# CLK_PWR.net
KiCad netlist of a schematic drawn in Altium Designer
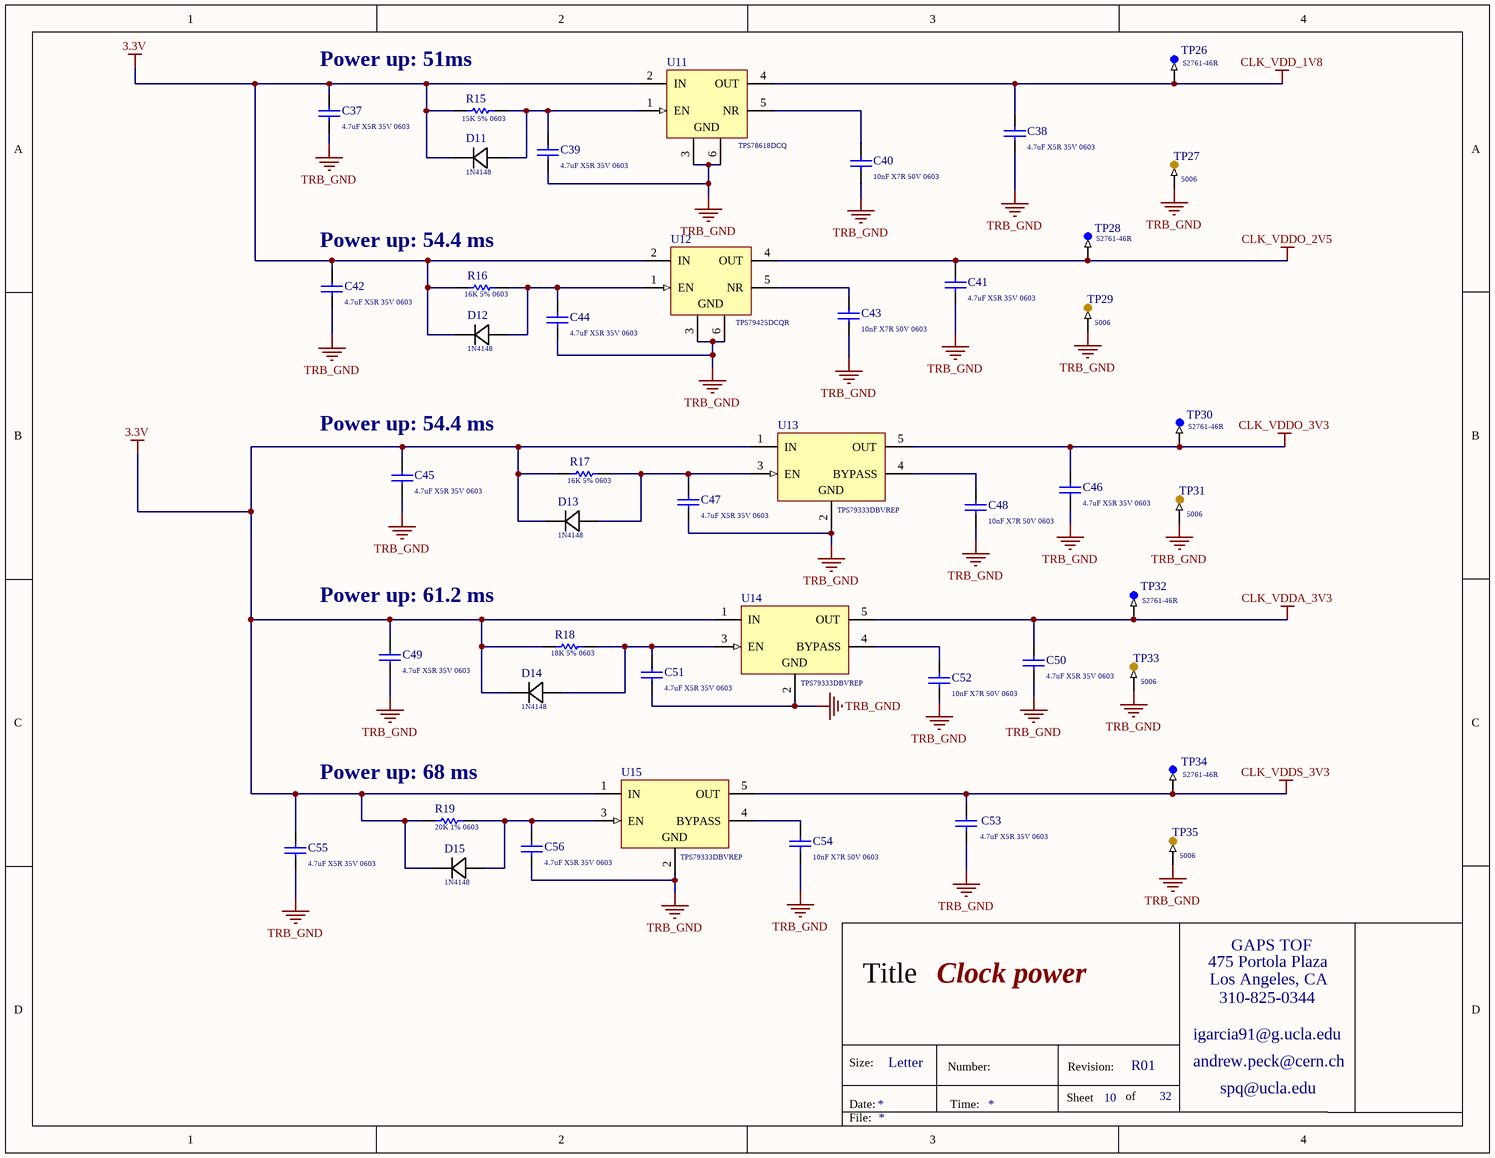
[diagram p0: CLK_PWR.SchDoc]

(export (version "E")
  (design (tool "Eeschema 10.0.6"))
  (components
    (comp (ref "C37")
      (value "Cap_Murata_ZRB18AR6YA475ME05L_4.7uF")
      (footprint "Cap_Murata_ZRB18AR6YA475ME05L_4.7uF")
      (description "CAP CER 4.7uF 35V X5R 0603")
      (fields (field (name "CAPACITANCE") "4.7uF X5R 35V 0603"))
      (libsource (lib "Cap_Murata_ZRB18AR6YA475ME05L_4.7uF") (part "Cap_Murata_ZRB18AR6YA475ME05L_4.7uF"))
    )
    (comp (ref "C38")
      (value "Cap_Murata_ZRB18AR6YA475ME05L_4.7uF")
      (footprint "Cap_Murata_ZRB18AR6YA475ME05L_4.7uF")
      (description "CAP CER 4.7uF 35V X5R 0603")
      (fields (field (name "CAPACITANCE") "4.7uF X5R 35V 0603"))
      (libsource (lib "Cap_Murata_ZRB18AR6YA475ME05L_4.7uF") (part "Cap_Murata_ZRB18AR6YA475ME05L_4.7uF"))
    )
    (comp (ref "C39")
      (value "Cap_Murata_ZRB18AR6YA475ME05L_4.7uF")
      (footprint "Cap_Murata_ZRB18AR6YA475ME05L_4.7uF")
      (description "CAP CER 4.7uF 35V X5R 0603")
      (fields (field (name "CAPACITANCE") "4.7uF X5R 35V 0603"))
      (libsource (lib "Cap_Murata_ZRB18AR6YA475ME05L_4.7uF") (part "Cap_Murata_ZRB18AR6YA475ME05L_4.7uF"))
    )
    (comp (ref "C40")
      (value "Cap_Kemet_C0603C103J5RACTU_eec")
      (footprint "Kemet_C0603_0")
      (description "CAP CER 10nF 50V X7R 0603")
      (fields
        (field (name "PART NUMBER") "C0603C103J5RACTU")
        (field (name "MANUFACTURER") "Kemet")
        (field (name "CAPACITANCE") "10nF X7R 50V 0603")
      )
      (libsource (lib "Cap_Kemet_C0603C103J5RACTU_10nF") (part "Cap_Kemet_C0603C103J5RACTU_eec"))
    )
    (comp (ref "C41")
      (value "Cap_Murata_ZRB18AR6YA475ME05L_4.7uF")
      (footprint "Cap_Murata_ZRB18AR6YA475ME05L_4.7uF")
      (description "CAP CER 4.7uF 35V X5R 0603")
      (fields (field (name "CAPACITANCE") "4.7uF X5R 35V 0603"))
      (libsource (lib "Cap_Murata_ZRB18AR6YA475ME05L_4.7uF") (part "Cap_Murata_ZRB18AR6YA475ME05L_4.7uF"))
    )
    (comp (ref "C42")
      (value "Cap_Murata_ZRB18AR6YA475ME05L_4.7uF")
      (footprint "Cap_Murata_ZRB18AR6YA475ME05L_4.7uF")
      (description "CAP CER 4.7uF 35V X5R 0603")
      (fields (field (name "CAPACITANCE") "4.7uF X5R 35V 0603"))
      (libsource (lib "Cap_Murata_ZRB18AR6YA475ME05L_4.7uF") (part "Cap_Murata_ZRB18AR6YA475ME05L_4.7uF"))
    )
    (comp (ref "C43")
      (value "Cap_Kemet_C0603C103J5RACTU_eec")
      (footprint "Kemet_C0603_0")
      (description "CAP CER 10nF 50V X7R 0603")
      (fields
        (field (name "PART NUMBER") "C0603C103J5RACTU")
        (field (name "MANUFACTURER") "Kemet")
        (field (name "CAPACITANCE") "10nF X7R 50V 0603")
      )
      (libsource (lib "Cap_Kemet_C0603C103J5RACTU_10nF") (part "Cap_Kemet_C0603C103J5RACTU_eec"))
    )
    (comp (ref "C44")
      (value "Cap_Murata_ZRB18AR6YA475ME05L_4.7uF")
      (footprint "Cap_Murata_ZRB18AR6YA475ME05L_4.7uF")
      (description "CAP CER 4.7uF 35V X5R 0603")
      (fields (field (name "CAPACITANCE") "4.7uF X5R 35V 0603"))
      (libsource (lib "Cap_Murata_ZRB18AR6YA475ME05L_4.7uF") (part "Cap_Murata_ZRB18AR6YA475ME05L_4.7uF"))
    )
    (comp (ref "C45")
      (value "Cap_Murata_ZRB18AR6YA475ME05L_4.7uF")
      (footprint "Cap_Murata_ZRB18AR6YA475ME05L_4.7uF")
      (description "CAP CER 4.7uF 35V X5R 0603")
      (fields (field (name "CAPACITANCE") "4.7uF X5R 35V 0603"))
      (libsource (lib "Cap_Murata_ZRB18AR6YA475ME05L_4.7uF") (part "Cap_Murata_ZRB18AR6YA475ME05L_4.7uF"))
    )
    (comp (ref "C46")
      (value "Cap_Murata_ZRB18AR6YA475ME05L_4.7uF")
      (footprint "Cap_Murata_ZRB18AR6YA475ME05L_4.7uF")
      (description "CAP CER 4.7uF 35V X5R 0603")
      (fields (field (name "CAPACITANCE") "4.7uF X5R 35V 0603"))
      (libsource (lib "Cap_Murata_ZRB18AR6YA475ME05L_4.7uF") (part "Cap_Murata_ZRB18AR6YA475ME05L_4.7uF"))
    )
    (comp (ref "C47")
      (value "Cap_Murata_ZRB18AR6YA475ME05L_4.7uF")
      (footprint "Cap_Murata_ZRB18AR6YA475ME05L_4.7uF")
      (description "CAP CER 4.7uF 35V X5R 0603")
      (fields (field (name "CAPACITANCE") "4.7uF X5R 35V 0603"))
      (libsource (lib "Cap_Murata_ZRB18AR6YA475ME05L_4.7uF") (part "Cap_Murata_ZRB18AR6YA475ME05L_4.7uF"))
    )
    (comp (ref "C48")
      (value "Cap_Kemet_C0603C103J5RACTU_eec")
      (footprint "Kemet_C0603_0")
      (description "CAP CER 10nF 50V X7R 0603")
      (fields
        (field (name "PART NUMBER") "C0603C103J5RACTU")
        (field (name "MANUFACTURER") "Kemet")
        (field (name "CAPACITANCE") "10nF X7R 50V 0603")
      )
      (libsource (lib "Cap_Kemet_C0603C103J5RACTU_10nF") (part "Cap_Kemet_C0603C103J5RACTU_eec"))
    )
    (comp (ref "C49")
      (value "Cap_Murata_ZRB18AR6YA475ME05L_4.7uF")
      (footprint "Cap_Murata_ZRB18AR6YA475ME05L_4.7uF")
      (description "CAP CER 4.7uF 35V X5R 0603")
      (fields (field (name "CAPACITANCE") "4.7uF X5R 35V 0603"))
      (libsource (lib "Cap_Murata_ZRB18AR6YA475ME05L_4.7uF") (part "Cap_Murata_ZRB18AR6YA475ME05L_4.7uF"))
    )
    (comp (ref "C50")
      (value "Cap_Murata_ZRB18AR6YA475ME05L_4.7uF")
      (footprint "Cap_Murata_ZRB18AR6YA475ME05L_4.7uF")
      (description "CAP CER 4.7uF 35V X5R 0603")
      (fields (field (name "CAPACITANCE") "4.7uF X5R 35V 0603"))
      (libsource (lib "Cap_Murata_ZRB18AR6YA475ME05L_4.7uF") (part "Cap_Murata_ZRB18AR6YA475ME05L_4.7uF"))
    )
    (comp (ref "C51")
      (value "Cap_Murata_ZRB18AR6YA475ME05L_4.7uF")
      (footprint "Cap_Murata_ZRB18AR6YA475ME05L_4.7uF")
      (description "CAP CER 4.7uF 35V X5R 0603")
      (fields (field (name "CAPACITANCE") "4.7uF X5R 35V 0603"))
      (libsource (lib "Cap_Murata_ZRB18AR6YA475ME05L_4.7uF") (part "Cap_Murata_ZRB18AR6YA475ME05L_4.7uF"))
    )
    (comp (ref "C52")
      (value "Cap_Kemet_C0603C103J5RACTU_eec")
      (footprint "Kemet_C0603_0")
      (description "CAP CER 10nF 50V X7R 0603")
      (fields
        (field (name "PART NUMBER") "C0603C103J5RACTU")
        (field (name "MANUFACTURER") "Kemet")
        (field (name "CAPACITANCE") "10nF X7R 50V 0603")
      )
      (libsource (lib "Cap_Kemet_C0603C103J5RACTU_10nF") (part "Cap_Kemet_C0603C103J5RACTU_eec"))
    )
    (comp (ref "C53")
      (value "Cap_Murata_ZRB18AR6YA475ME05L_4.7uF")
      (footprint "Cap_Murata_ZRB18AR6YA475ME05L_4.7uF")
      (description "CAP CER 4.7uF 35V X5R 0603")
      (fields (field (name "CAPACITANCE") "4.7uF X5R 35V 0603"))
      (libsource (lib "Cap_Murata_ZRB18AR6YA475ME05L_4.7uF") (part "Cap_Murata_ZRB18AR6YA475ME05L_4.7uF"))
    )
    (comp (ref "C54")
      (value "Cap_Kemet_C0603C103J5RACTU_eec")
      (footprint "Kemet_C0603_0")
      (description "CAP CER 10nF 50V X7R 0603")
      (fields
        (field (name "PART NUMBER") "C0603C103J5RACTU")
        (field (name "MANUFACTURER") "Kemet")
        (field (name "CAPACITANCE") "10nF X7R 50V 0603")
      )
      (libsource (lib "Cap_Kemet_C0603C103J5RACTU_10nF") (part "Cap_Kemet_C0603C103J5RACTU_eec"))
    )
    (comp (ref "C55")
      (value "Cap_Murata_ZRB18AR6YA475ME05L_4.7uF")
      (footprint "Cap_Murata_ZRB18AR6YA475ME05L_4.7uF")
      (description "CAP CER 4.7uF 35V X5R 0603")
      (fields (field (name "CAPACITANCE") "4.7uF X5R 35V 0603"))
      (libsource (lib "Cap_Murata_ZRB18AR6YA475ME05L_4.7uF") (part "Cap_Murata_ZRB18AR6YA475ME05L_4.7uF"))
    )
    (comp (ref "C56")
      (value "Cap_Murata_ZRB18AR6YA475ME05L_4.7uF")
      (footprint "Cap_Murata_ZRB18AR6YA475ME05L_4.7uF")
      (description "CAP CER 4.7uF 35V X5R 0603")
      (fields (field (name "CAPACITANCE") "4.7uF X5R 35V 0603"))
      (libsource (lib "Cap_Murata_ZRB18AR6YA475ME05L_4.7uF") (part "Cap_Murata_ZRB18AR6YA475ME05L_4.7uF"))
    )
    (comp (ref "D11")
      (value "Diode_ON_Semiconductor_1N4148WT_300mA")
      (footprint "Diode_ON_Semiconductor_1N4148WT_300mA")
      (description "Diodes - General Purpose, Power, Switching SINGLE JUNC. 75V 4.0NS COMP")
      (fields (field (name "SERIES") "1N4148"))
      (libsource (lib "Diode_ON_Semiconductor_1N4148WT_300mA") (part "Diode_ON_Semiconductor_1N4148WT_300mA"))
    )
    (comp (ref "D12")
      (value "Diode_ON_Semiconductor_1N4148WT_300mA")
      (footprint "Diode_ON_Semiconductor_1N4148WT_300mA")
      (description "Diodes - General Purpose, Power, Switching SINGLE JUNC. 75V 4.0NS COMP")
      (fields (field (name "SERIES") "1N4148"))
      (libsource (lib "Diode_ON_Semiconductor_1N4148WT_300mA") (part "Diode_ON_Semiconductor_1N4148WT_300mA"))
    )
    (comp (ref "D13")
      (value "Diode_ON_Semiconductor_1N4148WT_300mA")
      (footprint "Diode_ON_Semiconductor_1N4148WT_300mA")
      (description "Diodes - General Purpose, Power, Switching SINGLE JUNC. 75V 4.0NS COMP")
      (fields (field (name "SERIES") "1N4148"))
      (libsource (lib "Diode_ON_Semiconductor_1N4148WT_300mA") (part "Diode_ON_Semiconductor_1N4148WT_300mA"))
    )
    (comp (ref "D14")
      (value "Diode_ON_Semiconductor_1N4148WT_300mA")
      (footprint "Diode_ON_Semiconductor_1N4148WT_300mA")
      (description "Diodes - General Purpose, Power, Switching SINGLE JUNC. 75V 4.0NS COMP")
      (fields (field (name "SERIES") "1N4148"))
      (libsource (lib "Diode_ON_Semiconductor_1N4148WT_300mA") (part "Diode_ON_Semiconductor_1N4148WT_300mA"))
    )
    (comp (ref "D15")
      (value "Diode_ON_Semiconductor_1N4148WT_300mA")
      (footprint "Diode_ON_Semiconductor_1N4148WT_300mA")
      (description "Diodes - General Purpose, Power, Switching SINGLE JUNC. 75V 4.0NS COMP")
      (fields (field (name "SERIES") "1N4148"))
      (libsource (lib "Diode_ON_Semiconductor_1N4148WT_300mA") (part "Diode_ON_Semiconductor_1N4148WT_300mA"))
    )
    (comp (ref "R15")
      (value "15K 5% 0603")
      (footprint "RESC0603(1608)_L")
      (description "15K 0.1W 5% 0603 (1608 Metric)  SMD")
      (fields (field (name "POWER") "0.1 W") (field (name "TOLERANCE") "5 %"))
      (libsource (lib "Altium Content Vault") (part "RES"))
    )
    (comp (ref "R16")
      (value "16K 5% 0603")
      (footprint "RESC0603(1608)_L")
      (description "16K 0.1W 5% 0603 (1608 Metric)  SMD")
      (fields (field (name "TOLERANCE") "5 %") (field (name "POWER") "0.1 W"))
      (libsource (lib "Altium Content Vault") (part "RES"))
    )
    (comp (ref "R17")
      (value "16K 5% 0603")
      (footprint "RESC0603(1608)_L")
      (description "16K 0.1W 5% 0603 (1608 Metric)  SMD")
      (fields (field (name "TOLERANCE") "5 %") (field (name "POWER") "0.1 W"))
      (libsource (lib "Altium Content Vault") (part "RES"))
    )
    (comp (ref "R18")
      (value "18K 5% 0603")
      (footprint "RESC0603(1608)_L")
      (description "18K 0.1W 5% 0603 (1608 Metric)  SMD")
      (fields (field (name "POWER") "0.1 W") (field (name "TOLERANCE") "5 %"))
      (libsource (lib "Altium Content Vault") (part "RES"))
    )
    (comp (ref "R19")
      (value "20K 1% 0603")
      (footprint "RESC0603(1608)_L")
      (description "20K 0.1W 1% 0603 (1608 Metric)  SMD")
      (fields (field (name "TOLERANCE") "1 %") (field (name "POWER") "0.1 W"))
      (libsource (lib "Altium Content Vault") (part "RES"))
    )
    (comp (ref "TP26")
      (value "TP_Harwin_S2761_46R")
      (footprint "TP_Harwin_S2761_46R")
      (description "Circuit Board Hardware - PCB SMT Mini Test Terminal, Reel")
      (fields (field (name "SERIES") "S2761-46R"))
      (libsource (lib "TP_Harwin_S2761_46R") (part "TP_Harwin_S2761_46R"))
    )
    (comp (ref "TP27")
      (value "TP_Keystone_Electronics_5006")
      (footprint "TP_Keystone_Electronics_5006")
      (description "Circuit Board Hardware - PCB TEST POINT BLK .063")
      (fields (field (name "SERIES") "5006"))
      (libsource (lib "TP_Keystone_Electronics_5006") (part "TP_Keystone_Electronics_5006"))
    )
    (comp (ref "TP28")
      (value "TP_Harwin_S2761_46R")
      (footprint "TP_Harwin_S2761_46R")
      (description "Circuit Board Hardware - PCB SMT Mini Test Terminal, Reel")
      (fields (field (name "SERIES") "S2761-46R"))
      (libsource (lib "TP_Harwin_S2761_46R") (part "TP_Harwin_S2761_46R"))
    )
    (comp (ref "TP29")
      (value "TP_Keystone_Electronics_5006")
      (footprint "TP_Keystone_Electronics_5006")
      (description "Circuit Board Hardware - PCB TEST POINT BLK .063")
      (fields (field (name "SERIES") "5006"))
      (libsource (lib "TP_Keystone_Electronics_5006") (part "TP_Keystone_Electronics_5006"))
    )
    (comp (ref "TP30")
      (value "TP_Harwin_S2761_46R")
      (footprint "TP_Harwin_S2761_46R")
      (description "Circuit Board Hardware - PCB SMT Mini Test Terminal, Reel")
      (fields (field (name "SERIES") "S2761-46R"))
      (libsource (lib "TP_Harwin_S2761_46R") (part "TP_Harwin_S2761_46R"))
    )
    (comp (ref "TP31")
      (value "TP_Keystone_Electronics_5006")
      (footprint "TP_Keystone_Electronics_5006")
      (description "Circuit Board Hardware - PCB TEST POINT BLK .063")
      (fields (field (name "SERIES") "5006"))
      (libsource (lib "TP_Keystone_Electronics_5006") (part "TP_Keystone_Electronics_5006"))
    )
    (comp (ref "TP32")
      (value "TP_Harwin_S2761_46R")
      (footprint "TP_Harwin_S2761_46R")
      (description "Circuit Board Hardware - PCB SMT Mini Test Terminal, Reel")
      (fields (field (name "SERIES") "S2761-46R"))
      (libsource (lib "TP_Harwin_S2761_46R") (part "TP_Harwin_S2761_46R"))
    )
    (comp (ref "TP33")
      (value "TP_Keystone_Electronics_5006")
      (footprint "TP_Keystone_Electronics_5006")
      (description "Circuit Board Hardware - PCB TEST POINT BLK .063")
      (fields (field (name "SERIES") "5006"))
      (libsource (lib "TP_Keystone_Electronics_5006") (part "TP_Keystone_Electronics_5006"))
    )
    (comp (ref "TP34")
      (value "TP_Harwin_S2761_46R")
      (footprint "TP_Harwin_S2761_46R")
      (description "Circuit Board Hardware - PCB SMT Mini Test Terminal, Reel")
      (fields (field (name "SERIES") "S2761-46R"))
      (libsource (lib "TP_Harwin_S2761_46R") (part "TP_Harwin_S2761_46R"))
    )
    (comp (ref "TP35")
      (value "TP_Keystone_Electronics_5006")
      (footprint "TP_Keystone_Electronics_5006")
      (description "Circuit Board Hardware - PCB TEST POINT BLK .063")
      (fields (field (name "SERIES") "5006"))
      (libsource (lib "TP_Keystone_Electronics_5006") (part "TP_Keystone_Electronics_5006"))
    )
    (comp (ref "U11")
      (value "TPS78618DCQ")
      (footprint "DCQ0006A_L")
      (fields (field (name "MANUFACTURER") "Texas Instruments"))
      (libsource (lib "Altium Content Vault") (part "TI-TPS7XXXXXXXX"))
    )
    (comp (ref "U12")
      (value "TPS79425DCQR")
      (footprint "DCQ0006A_L")
      (fields (field (name "MANUFACTURER") "Texas Instruments"))
      (libsource (lib "Altium Content Vault") (part "TI-TPS7XXXXXXXX"))
    )
    (comp (ref "U13")
      (value "TPS79333DBVREP")
      (footprint "DBV0005A_M")
      (fields (field (name "MANUFACTURER") "Texas Instruments"))
      (libsource (lib "TPS79333DBVREP") (part "CMP-0394-00316-2"))
    )
    (comp (ref "U14")
      (value "TPS79333DBVREP")
      (footprint "DBV0005A_M")
      (fields (field (name "MANUFACTURER") "Texas Instruments"))
      (libsource (lib "TPS79333DBVREP") (part "CMP-0394-00316-2"))
    )
    (comp (ref "U15")
      (value "TPS79333DBVREP")
      (footprint "DBV0005A_M")
      (fields (field (name "MANUFACTURER") "Texas Instruments"))
      (libsource (lib "TPS79333DBVREP") (part "CMP-0394-00316-2"))
    )
  )
  (nets
    (net (code "1") (name "3.3V") (class "Default")
      (node (ref "C37") (pin "2") (pinfunction "2_2") (pintype "passive"))
      (node (ref "C42") (pin "2") (pinfunction "2_2") (pintype "passive"))
      (node (ref "C45") (pin "2") (pinfunction "2_2") (pintype "passive"))
      (node (ref "C49") (pin "2") (pinfunction "2_2") (pintype "passive"))
      (node (ref "C55") (pin "2") (pinfunction "2_2") (pintype "passive"))
      (node (ref "D11") (pin "1") (pinfunction "1_1") (pintype "passive"))
      (node (ref "D12") (pin "1") (pinfunction "1_1") (pintype "passive"))
      (node (ref "D13") (pin "1") (pinfunction "1_1") (pintype "passive"))
      (node (ref "D14") (pin "1") (pinfunction "1_1") (pintype "passive"))
      (node (ref "D15") (pin "1") (pinfunction "1_1") (pintype "passive"))
      (node (ref "R15") (pin "1") (pinfunction "1_1") (pintype "passive"))
      (node (ref "R16") (pin "1") (pinfunction "1_1") (pintype "passive"))
      (node (ref "R17") (pin "1") (pinfunction "1_1") (pintype "passive"))
      (node (ref "R18") (pin "1") (pinfunction "1_1") (pintype "passive"))
      (node (ref "R19") (pin "2") (pinfunction "2_2") (pintype "passive"))
      (node (ref "U11") (pin "2") (pinfunction "IN_2") (pintype "power_in"))
      (node (ref "U12") (pin "2") (pinfunction "IN_2") (pintype "power_in"))
      (node (ref "U13") (pin "1") (pinfunction "IN_1") (pintype "power_in"))
      (node (ref "U14") (pin "1") (pinfunction "IN_1") (pintype "power_in"))
      (node (ref "U15") (pin "1") (pinfunction "IN_1") (pintype "power_in"))
    )
    (net (code "2") (name "CLK_VDDA_3V3") (class "Default")
      (node (ref "C50") (pin "2") (pinfunction "2_2") (pintype "passive"))
      (node (ref "TP32") (pin "1") (pinfunction "1_1") (pintype "input"))
      (node (ref "U14") (pin "5") (pinfunction "OUT_5") (pintype "power_in"))
    )
    (net (code "3") (name "CLK_VDDO_2V5") (class "Default")
      (node (ref "C41") (pin "2") (pinfunction "2_2") (pintype "passive"))
      (node (ref "TP28") (pin "1") (pinfunction "1_1") (pintype "input"))
      (node (ref "U12") (pin "4") (pinfunction "OUT_4") (pintype "power_in"))
    )
    (net (code "4") (name "CLK_VDDO_3V3") (class "Default")
      (node (ref "C46") (pin "2") (pinfunction "2_2") (pintype "passive"))
      (node (ref "TP30") (pin "1") (pinfunction "1_1") (pintype "input"))
      (node (ref "U13") (pin "5") (pinfunction "OUT_5") (pintype "power_in"))
    )
    (net (code "5") (name "CLK_VDDS_3V3") (class "Default")
      (node (ref "C53") (pin "2") (pinfunction "2_2") (pintype "passive"))
      (node (ref "TP34") (pin "1") (pinfunction "1_1") (pintype "input"))
      (node (ref "U15") (pin "5") (pinfunction "OUT_5") (pintype "power_in"))
    )
    (net (code "6") (name "CLK_VDD_1V8") (class "Default")
      (node (ref "C38") (pin "2") (pinfunction "2_2") (pintype "passive"))
      (node (ref "TP26") (pin "1") (pinfunction "1_1") (pintype "input"))
      (node (ref "U11") (pin "4") (pinfunction "OUT_4") (pintype "power_in"))
    )
    (net (code "7") (name "Net-(U11-EN)") (class "Default")
      (node (ref "C39") (pin "2") (pinfunction "2_2") (pintype "passive"))
      (node (ref "D11") (pin "2") (pinfunction "2_2") (pintype "passive"))
      (node (ref "R15") (pin "2") (pinfunction "2_2") (pintype "passive"))
      (node (ref "U11") (pin "1") (pinfunction "EN_1") (pintype "input"))
    )
    (net (code "8") (name "Net-(U11-NR)") (class "Default")
      (node (ref "C40") (pin "1") (pinfunction "1_1") (pintype "passive"))
      (node (ref "U11") (pin "5") (pinfunction "NR_5") (pintype "passive"))
    )
    (net (code "9") (name "Net-(U12-EN)") (class "Default")
      (node (ref "C44") (pin "2") (pinfunction "2_2") (pintype "passive"))
      (node (ref "D12") (pin "2") (pinfunction "2_2") (pintype "passive"))
      (node (ref "R16") (pin "2") (pinfunction "2_2") (pintype "passive"))
      (node (ref "U12") (pin "1") (pinfunction "EN_1") (pintype "input"))
    )
    (net (code "10") (name "Net-(U12-NR)") (class "Default")
      (node (ref "C43") (pin "1") (pinfunction "1_1") (pintype "passive"))
      (node (ref "U12") (pin "5") (pinfunction "NR_5") (pintype "passive"))
    )
    (net (code "11") (name "Net-(U13-BYPASS)") (class "Default")
      (node (ref "C48") (pin "1") (pinfunction "1_1") (pintype "passive"))
      (node (ref "U13") (pin "4") (pinfunction "BYPASS_4") (pintype "passive"))
    )
    (net (code "12") (name "Net-(U13-EN)") (class "Default")
      (node (ref "C47") (pin "2") (pinfunction "2_2") (pintype "passive"))
      (node (ref "D13") (pin "2") (pinfunction "2_2") (pintype "passive"))
      (node (ref "R17") (pin "2") (pinfunction "2_2") (pintype "passive"))
      (node (ref "U13") (pin "3") (pinfunction "EN_3") (pintype "input"))
    )
    (net (code "13") (name "Net-(U14-BYPASS)") (class "Default")
      (node (ref "C52") (pin "1") (pinfunction "1_1") (pintype "passive"))
      (node (ref "U14") (pin "4") (pinfunction "BYPASS_4") (pintype "passive"))
    )
    (net (code "14") (name "Net-(U14-EN)") (class "Default")
      (node (ref "C51") (pin "2") (pinfunction "2_2") (pintype "passive"))
      (node (ref "D14") (pin "2") (pinfunction "2_2") (pintype "passive"))
      (node (ref "R18") (pin "2") (pinfunction "2_2") (pintype "passive"))
      (node (ref "U14") (pin "3") (pinfunction "EN_3") (pintype "input"))
    )
    (net (code "15") (name "Net-(U15-BYPASS)") (class "Default")
      (node (ref "C54") (pin "1") (pinfunction "1_1") (pintype "passive"))
      (node (ref "U15") (pin "4") (pinfunction "BYPASS_4") (pintype "passive"))
    )
    (net (code "16") (name "Net-(U15-EN)") (class "Default")
      (node (ref "C56") (pin "2") (pinfunction "2_2") (pintype "passive"))
      (node (ref "D15") (pin "2") (pinfunction "2_2") (pintype "passive"))
      (node (ref "R19") (pin "1") (pinfunction "1_1") (pintype "passive"))
      (node (ref "U15") (pin "3") (pinfunction "EN_3") (pintype "input"))
    )
    (net (code "17") (name "TRB_GND") (class "Default")
      (node (ref "C37") (pin "1") (pinfunction "1_1") (pintype "passive"))
      (node (ref "C38") (pin "1") (pinfunction "1_1") (pintype "passive"))
      (node (ref "C39") (pin "1") (pinfunction "1_1") (pintype "passive"))
      (node (ref "C40") (pin "2") (pinfunction "2_2") (pintype "passive"))
      (node (ref "C41") (pin "1") (pinfunction "1_1") (pintype "passive"))
      (node (ref "C42") (pin "1") (pinfunction "1_1") (pintype "passive"))
      (node (ref "C43") (pin "2") (pinfunction "2_2") (pintype "passive"))
      (node (ref "C44") (pin "1") (pinfunction "1_1") (pintype "passive"))
      (node (ref "C45") (pin "1") (pinfunction "1_1") (pintype "passive"))
      (node (ref "C46") (pin "1") (pinfunction "1_1") (pintype "passive"))
      (node (ref "C47") (pin "1") (pinfunction "1_1") (pintype "passive"))
      (node (ref "C48") (pin "2") (pinfunction "2_2") (pintype "passive"))
      (node (ref "C49") (pin "1") (pinfunction "1_1") (pintype "passive"))
      (node (ref "C50") (pin "1") (pinfunction "1_1") (pintype "passive"))
      (node (ref "C51") (pin "1") (pinfunction "1_1") (pintype "passive"))
      (node (ref "C52") (pin "2") (pinfunction "2_2") (pintype "passive"))
      (node (ref "C53") (pin "1") (pinfunction "1_1") (pintype "passive"))
      (node (ref "C54") (pin "2") (pinfunction "2_2") (pintype "passive"))
      (node (ref "C55") (pin "1") (pinfunction "1_1") (pintype "passive"))
      (node (ref "C56") (pin "1") (pinfunction "1_1") (pintype "passive"))
      (node (ref "TP27") (pin "1") (pinfunction "1_1") (pintype "input"))
      (node (ref "TP29") (pin "1") (pinfunction "1_1") (pintype "input"))
      (node (ref "TP31") (pin "1") (pinfunction "1_1") (pintype "input"))
      (node (ref "TP33") (pin "1") (pinfunction "1_1") (pintype "input"))
      (node (ref "TP35") (pin "1") (pinfunction "1_1") (pintype "input"))
      (node (ref "U11") (pin "3") (pinfunction "GND_3") (pintype "power_in"))
      (node (ref "U11") (pin "6") (pinfunction "GND_6") (pintype "power_in"))
      (node (ref "U12") (pin "3") (pinfunction "GND_3") (pintype "power_in"))
      (node (ref "U12") (pin "6") (pinfunction "GND_6") (pintype "power_in"))
      (node (ref "U13") (pin "2") (pinfunction "GND_2") (pintype "power_in"))
      (node (ref "U14") (pin "2") (pinfunction "GND_2") (pintype "power_in"))
      (node (ref "U15") (pin "2") (pinfunction "GND_2") (pintype "power_in"))
    )
  )
)
